# simple_bezel.net
KiCad netlist of a schematic drawn in Altium Designer
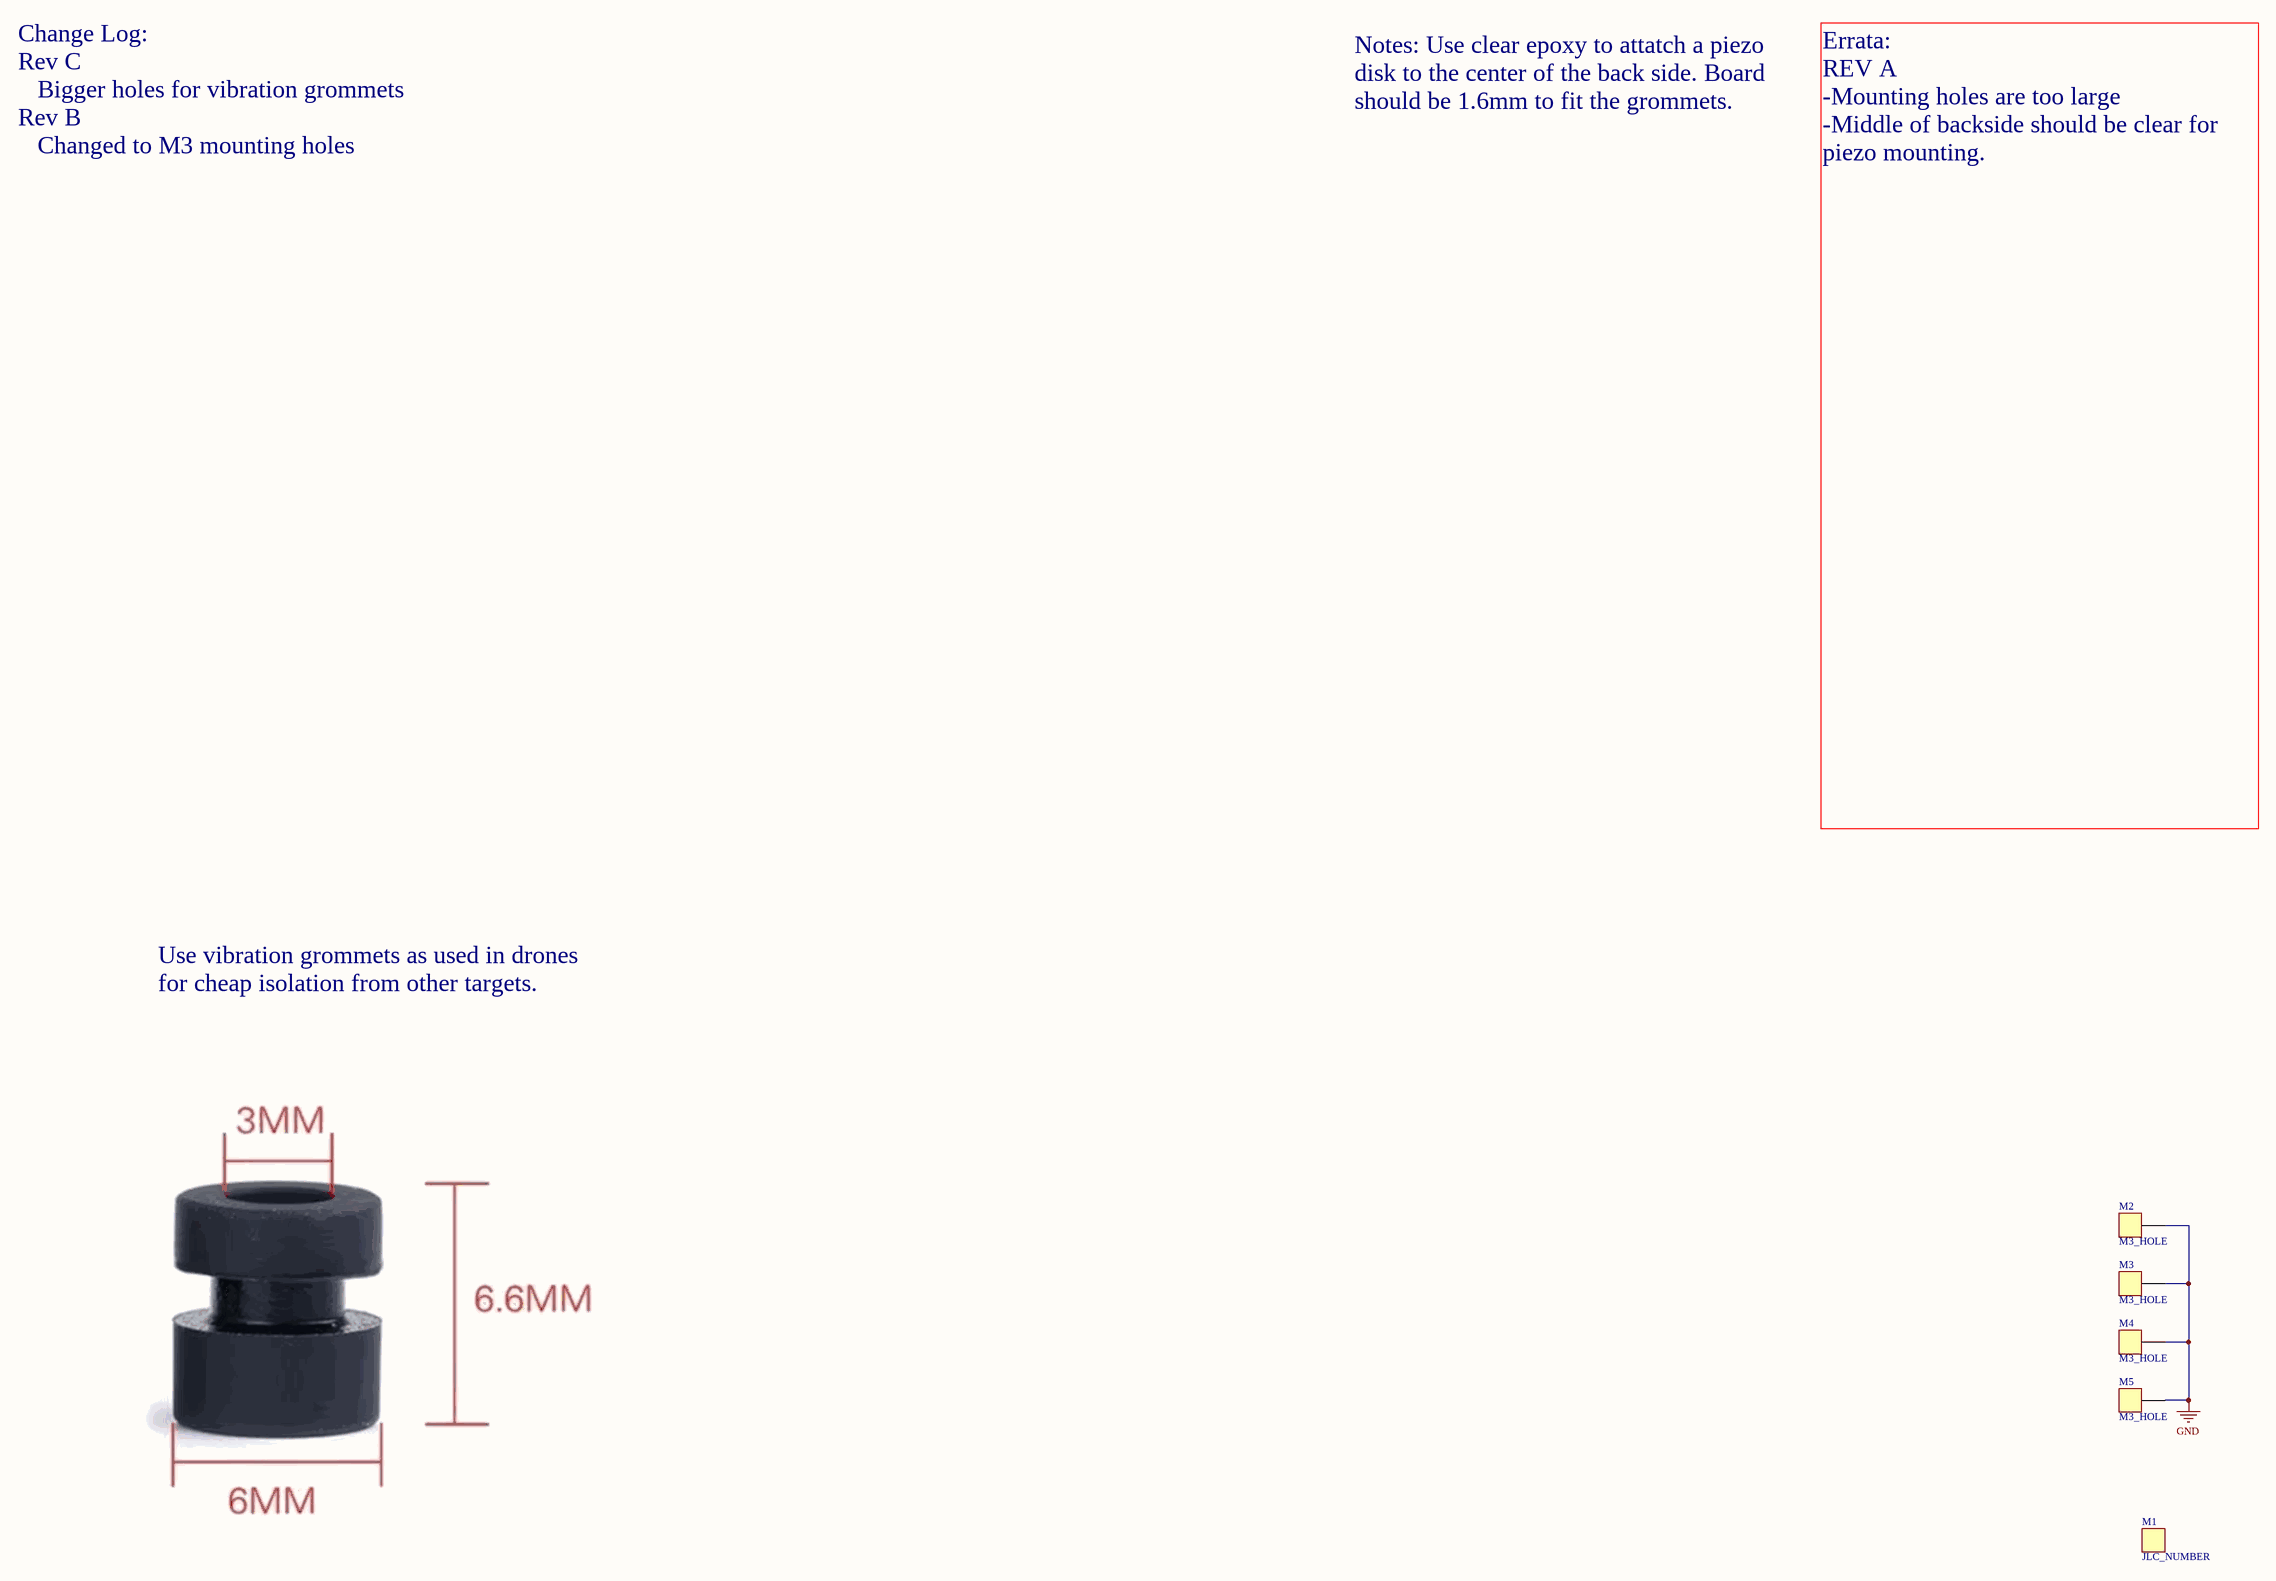
[diagram p0: simple_bezel.SchDoc]

(export (version "E")
  (design (tool "Eeschema 10.0.6"))
  (components
    (comp (ref "M1")
      (value "JLC_NUMBER")
      (footprint "JLC_NUMBER")
      (description "JLC Order Number Location")
      (libsource (lib "Mechanical") (part "MECH_NO_BOM"))
    )
    (comp (ref "M2")
      (value "M3_HOLE")
      (footprint "M3_HOLE")
      (libsource (lib "Mechanical") (part "MECH_1PIN_NO_BOM"))
    )
    (comp (ref "M3")
      (value "M3_HOLE")
      (footprint "M3_HOLE")
      (libsource (lib "Mechanical") (part "MECH_1PIN_NO_BOM"))
    )
    (comp (ref "M4")
      (value "M3_HOLE")
      (footprint "M3_HOLE")
      (libsource (lib "Mechanical") (part "MECH_1PIN_NO_BOM"))
    )
    (comp (ref "M5")
      (value "M3_HOLE")
      (footprint "M3_HOLE")
      (libsource (lib "Mechanical") (part "MECH_1PIN_NO_BOM"))
    )
  )
  (nets
    (net (code "1") (name "GND") (class "Default")
      (node (ref "M2") (pin "1") (pinfunction "1_1") (pintype "passive"))
      (node (ref "M3") (pin "1") (pinfunction "1_1") (pintype "passive"))
      (node (ref "M4") (pin "1") (pinfunction "1_1") (pintype "passive"))
      (node (ref "M5") (pin "1") (pinfunction "1_1") (pintype "passive"))
    )
  )
)
